# Templates.net
KiCad netlist of a schematic drawn in Altium Designer
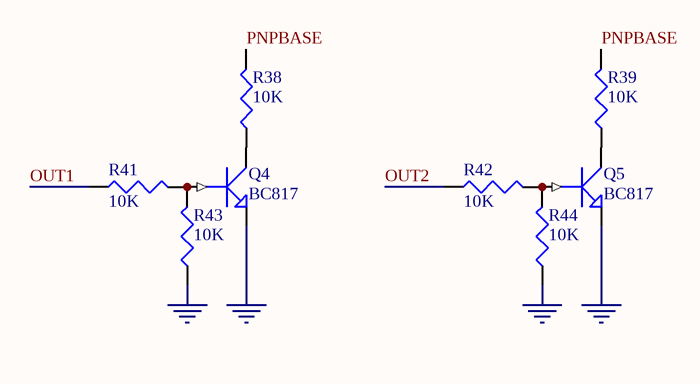
[diagram p0: Templates.SCHDOC]

(export (version "E")
  (design (tool "Eeschema 10.0.6"))
  (components
    (comp (ref "Q4")
      (value "BC817")
      (footprint "SOT-23")
      (description "NPN Transistor")
      (libsource (lib "Miscellaneous Devices") (part "NPN1"))
    )
    (comp (ref "Q5")
      (value "BC817")
      (footprint "SOT-23")
      (description "NPN Transistor")
      (libsource (lib "Miscellaneous Devices") (part "NPN1"))
    )
    (comp (ref "R38")
      (value "10K")
      (footprint "0805")
      (libsource (lib "Miscellaneous Devices") (part "RES1"))
    )
    (comp (ref "R39")
      (value "10K")
      (footprint "0805")
      (libsource (lib "Miscellaneous Devices") (part "RES1"))
    )
    (comp (ref "R41")
      (value "10K")
      (footprint "0603")
      (libsource (lib "Miscellaneous Devices") (part "RES1"))
    )
    (comp (ref "R42")
      (value "10K")
      (footprint "0805")
      (libsource (lib "Miscellaneous Devices") (part "RES1"))
    )
    (comp (ref "R43")
      (value "10K")
      (footprint "0805")
      (libsource (lib "Miscellaneous Devices") (part "RES1"))
    )
    (comp (ref "R44")
      (value "10K")
      (footprint "0805")
      (libsource (lib "Miscellaneous Devices") (part "RES1"))
    )
  )
  (nets
    (net (code "1") (name "/OUT1") (class "Default")
      (node (ref "R41") (pin "1") (pinfunction "1_1") (pintype "passive"))
    )
    (net (code "2") (name "/OUT2") (class "Default")
      (node (ref "R42") (pin "1") (pinfunction "1_1") (pintype "passive"))
    )
    (net (code "3") (name "/PNPBASE") (class "Default")
      (node (ref "R38") (pin "2") (pinfunction "2_2") (pintype "passive"))
      (node (ref "R39") (pin "2") (pinfunction "2_2") (pintype "passive"))
    )
    (net (code "4") (name "GND") (class "Default")
      (node (ref "Q4") (pin "3") (pinfunction "E_3") (pintype "passive"))
      (node (ref "Q5") (pin "3") (pinfunction "E_3") (pintype "passive"))
      (node (ref "R43") (pin "1") (pinfunction "1_1") (pintype "passive"))
      (node (ref "R44") (pin "1") (pinfunction "1_1") (pintype "passive"))
    )
    (net (code "5") (name "Net-(Q4-B)") (class "Default")
      (node (ref "Q4") (pin "1") (pinfunction "B_1") (pintype "input"))
      (node (ref "R41") (pin "2") (pinfunction "2_2") (pintype "passive"))
      (node (ref "R43") (pin "2") (pinfunction "2_2") (pintype "passive"))
    )
    (net (code "6") (name "Net-(Q4-C)") (class "Default")
      (node (ref "Q4") (pin "2") (pinfunction "C_2") (pintype "passive"))
      (node (ref "R38") (pin "1") (pinfunction "1_1") (pintype "passive"))
    )
    (net (code "7") (name "Net-(Q5-B)") (class "Default")
      (node (ref "Q5") (pin "1") (pinfunction "B_1") (pintype "input"))
      (node (ref "R42") (pin "2") (pinfunction "2_2") (pintype "passive"))
      (node (ref "R44") (pin "2") (pinfunction "2_2") (pintype "passive"))
    )
    (net (code "8") (name "Net-(Q5-C)") (class "Default")
      (node (ref "Q5") (pin "2") (pinfunction "C_2") (pintype "passive"))
      (node (ref "R39") (pin "1") (pinfunction "1_1") (pintype "passive"))
    )
  )
)
